# Esquema2.net
KiCad netlist of a schematic drawn in EAGLE
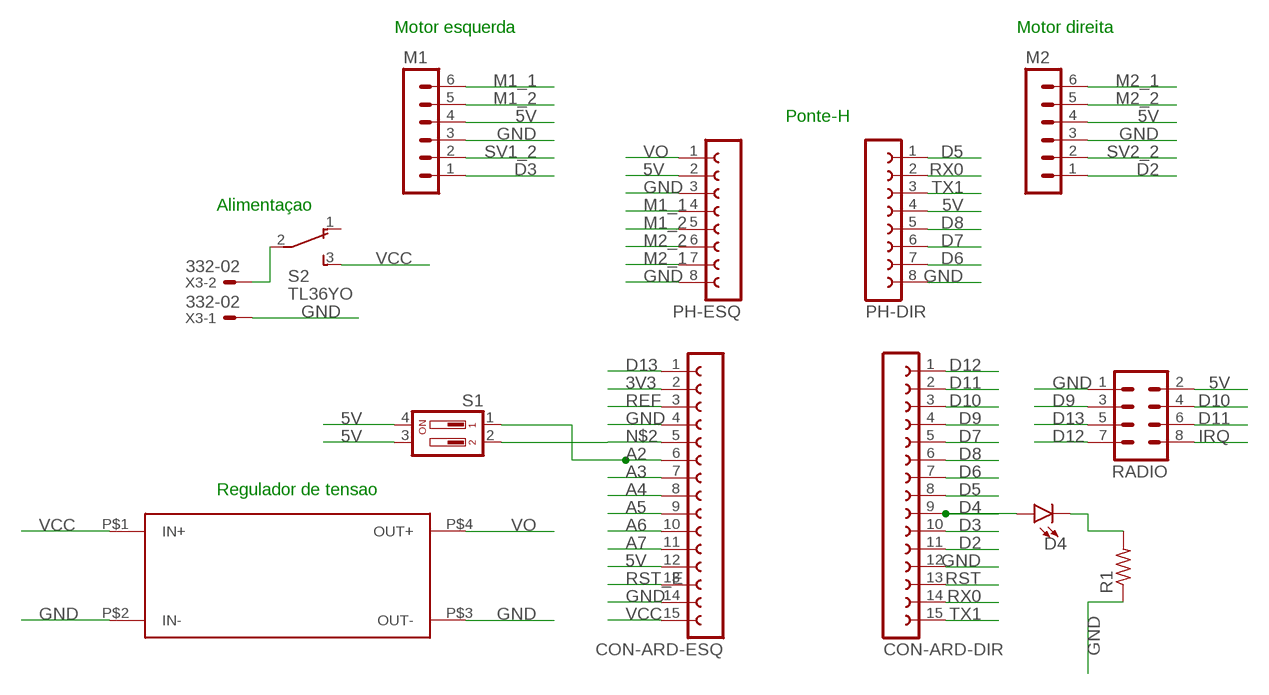
[diagram p0: schematic, sheet 1]

(export (version "E")
  (design (tool "Eeschema 10.0.6"))
  (components
    (comp (ref "CON-ARD-DIR")
      (value "FE15-1")
      (footprint "eagle-import:FE15")
      (libsource (lib "eagle-import") (part "FE15-1"))
    )
    (comp (ref "CON-ARD-ESQ")
      (value "FE15-1")
      (footprint "eagle-import:FE15")
      (fields (field (name "SPICEPREFIX") "X"))
      (libsource (lib "eagle-import") (part "FE15-1"))
    )
    (comp (ref "D4")
      (value "LED-3MM-NO_SILK")
      (footprint "eagle-import:LED_3MM-NS")
      (libsource (lib "eagle-import") (part "LED-3MM-NO_SILK"))
    )
    (comp (ref "M1")
      (value "MA06-1")
      (footprint "eagle-import:MA06-1")
      (libsource (lib "eagle-import") (part "MA06-1"))
    )
    (comp (ref "M2")
      (value "MA06-1")
      (footprint "eagle-import:MA06-1")
      (libsource (lib "eagle-import") (part "MA06-1"))
    )
    (comp (ref "PH-DIR")
      (value "FE08-1")
      (footprint "eagle-import:FE08")
      (libsource (lib "eagle-import") (part "FE08-1"))
    )
    (comp (ref "PH-ESQ")
      (value "FE08-1")
      (footprint "eagle-import:FE08")
      (libsource (lib "eagle-import") (part "FE08-1"))
    )
    (comp (ref "R1")
      (value "R-US_0207/12")
      (footprint "eagle-import:0207_12")
      (libsource (lib "eagle-import") (part "R-US_0207/12"))
    )
    (comp (ref "RADIO")
      (value "MA04-2")
      (footprint "eagle-import:MA04-2")
      (libsource (lib "eagle-import") (part "MA04-2"))
    )
    (comp (ref "S1")
      (value "DA02")
      (footprint "eagle-import:DA-02")
      (libsource (lib "eagle-import") (part "DA02"))
    )
    (comp (ref "S2")
      (value "TL36YO")
      (footprint "eagle-import:TL3XYO")
      (libsource (lib "eagle-import") (part "TL36YO"))
    )
    (comp (ref "U$1")
      (value "REGULADOR")
      (footprint "eagle-import:REGULADOR-FP")
      (libsource (lib "eagle-import") (part "REGULADOR"))
    )
    (comp (ref "X3")
      (value "332-02")
      (footprint "eagle-import:332-02")
      (libsource (lib "eagle-import") (part "332-02"))
    )
  )
  (nets
    (net (code "1") (name "/3V3") (class "Default")
      (node (ref "CON-ARD-ESQ") (pin "2") (pinfunction "2_2") (pintype "passive"))
    )
    (net (code "2") (name "/5V") (class "Default")
      (node (ref "CON-ARD-ESQ") (pin "12") (pinfunction "12_12") (pintype "passive"))
      (node (ref "M1") (pin "4") (pinfunction "4_4") (pintype "passive"))
      (node (ref "M2") (pin "4") (pinfunction "4_4") (pintype "passive"))
      (node (ref "PH-DIR") (pin "4") (pinfunction "4_4") (pintype "passive"))
      (node (ref "PH-ESQ") (pin "2") (pinfunction "2_2") (pintype "passive"))
      (node (ref "RADIO") (pin "2") (pinfunction "2_2") (pintype "passive"))
      (node (ref "S1") (pin "3") (pinfunction "3_3") (pintype "passive"))
      (node (ref "S1") (pin "4") (pinfunction "4_4") (pintype "passive"))
    )
    (net (code "3") (name "/A2") (class "Default")
      (node (ref "CON-ARD-ESQ") (pin "6") (pinfunction "6_6") (pintype "passive"))
      (node (ref "S1") (pin "1") (pinfunction "1_1") (pintype "passive"))
    )
    (net (code "4") (name "/A3") (class "Default")
      (node (ref "CON-ARD-ESQ") (pin "7") (pinfunction "7_7") (pintype "passive"))
    )
    (net (code "5") (name "/A4") (class "Default")
      (node (ref "CON-ARD-ESQ") (pin "8") (pinfunction "8_8") (pintype "passive"))
    )
    (net (code "6") (name "/A5") (class "Default")
      (node (ref "CON-ARD-ESQ") (pin "9") (pinfunction "9_9") (pintype "passive"))
    )
    (net (code "7") (name "/A6") (class "Default")
      (node (ref "CON-ARD-ESQ") (pin "10") (pinfunction "10_10") (pintype "passive"))
    )
    (net (code "8") (name "/A7") (class "Default")
      (node (ref "CON-ARD-ESQ") (pin "11") (pinfunction "11_11") (pintype "passive"))
    )
    (net (code "9") (name "/D2") (class "Default")
      (node (ref "CON-ARD-DIR") (pin "11") (pinfunction "11_11") (pintype "passive"))
      (node (ref "M2") (pin "1") (pinfunction "1_1") (pintype "passive"))
    )
    (net (code "10") (name "/D3") (class "Default")
      (node (ref "CON-ARD-DIR") (pin "10") (pinfunction "10_10") (pintype "passive"))
      (node (ref "M1") (pin "1") (pinfunction "1_1") (pintype "passive"))
    )
    (net (code "11") (name "/D4") (class "Default")
      (node (ref "CON-ARD-DIR") (pin "9") (pinfunction "9_9") (pintype "passive"))
      (node (ref "D4") (pin "A") (pinfunction "A_A") (pintype "passive"))
    )
    (net (code "12") (name "/D5") (class "Default")
      (node (ref "CON-ARD-DIR") (pin "8") (pinfunction "8_8") (pintype "passive"))
      (node (ref "PH-DIR") (pin "1") (pinfunction "1_1") (pintype "passive"))
    )
    (net (code "13") (name "/D6") (class "Default")
      (node (ref "CON-ARD-DIR") (pin "7") (pinfunction "7_7") (pintype "passive"))
      (node (ref "PH-DIR") (pin "7") (pinfunction "7_7") (pintype "passive"))
    )
    (net (code "14") (name "/D7") (class "Default")
      (node (ref "CON-ARD-DIR") (pin "5") (pinfunction "5_5") (pintype "passive"))
      (node (ref "PH-DIR") (pin "6") (pinfunction "6_6") (pintype "passive"))
    )
    (net (code "15") (name "/D8") (class "Default")
      (node (ref "CON-ARD-DIR") (pin "6") (pinfunction "6_6") (pintype "passive"))
      (node (ref "PH-DIR") (pin "5") (pinfunction "5_5") (pintype "passive"))
    )
    (net (code "16") (name "/D9") (class "Default")
      (node (ref "CON-ARD-DIR") (pin "4") (pinfunction "4_4") (pintype "passive"))
      (node (ref "RADIO") (pin "3") (pinfunction "3_3") (pintype "passive"))
    )
    (net (code "17") (name "/D10") (class "Default")
      (node (ref "CON-ARD-DIR") (pin "3") (pinfunction "3_3") (pintype "passive"))
      (node (ref "RADIO") (pin "4") (pinfunction "4_4") (pintype "passive"))
    )
    (net (code "18") (name "/D11") (class "Default")
      (node (ref "CON-ARD-DIR") (pin "2") (pinfunction "2_2") (pintype "passive"))
      (node (ref "RADIO") (pin "6") (pinfunction "6_6") (pintype "passive"))
    )
    (net (code "19") (name "/D12") (class "Default")
      (node (ref "CON-ARD-DIR") (pin "1") (pinfunction "1_1") (pintype "passive"))
      (node (ref "RADIO") (pin "7") (pinfunction "7_7") (pintype "passive"))
    )
    (net (code "20") (name "/D13") (class "Default")
      (node (ref "CON-ARD-ESQ") (pin "1") (pinfunction "1_1") (pintype "passive"))
      (node (ref "RADIO") (pin "5") (pinfunction "5_5") (pintype "passive"))
    )
    (net (code "21") (name "/GND") (class "Default")
      (node (ref "CON-ARD-DIR") (pin "12") (pinfunction "12_12") (pintype "passive"))
      (node (ref "CON-ARD-ESQ") (pin "14") (pinfunction "14_14") (pintype "passive"))
      (node (ref "CON-ARD-ESQ") (pin "4") (pinfunction "4_4") (pintype "passive"))
      (node (ref "M1") (pin "3") (pinfunction "3_3") (pintype "passive"))
      (node (ref "M2") (pin "3") (pinfunction "3_3") (pintype "passive"))
      (node (ref "PH-DIR") (pin "8") (pinfunction "8_8") (pintype "passive"))
      (node (ref "PH-ESQ") (pin "3") (pinfunction "3_3") (pintype "passive"))
      (node (ref "PH-ESQ") (pin "8") (pinfunction "8_8") (pintype "passive"))
      (node (ref "R1") (pin "1") (pinfunction "1_1") (pintype "passive"))
      (node (ref "RADIO") (pin "1") (pinfunction "1_1") (pintype "passive"))
      (node (ref "U$1") (pin "P$2") (pinfunction "IN-_P$2") (pintype "bidirectional"))
      (node (ref "U$1") (pin "P$3") (pinfunction "OUT-_P$3") (pintype "bidirectional"))
      (node (ref "X3") (pin "1") (pinfunction "S_1") (pintype "passive"))
    )
    (net (code "22") (name "/IRQ") (class "Default")
      (node (ref "RADIO") (pin "8") (pinfunction "8_8") (pintype "passive"))
    )
    (net (code "23") (name "/M1_1") (class "Default")
      (node (ref "M1") (pin "6") (pinfunction "6_6") (pintype "passive"))
      (node (ref "PH-ESQ") (pin "4") (pinfunction "4_4") (pintype "passive"))
    )
    (net (code "24") (name "/M1_2") (class "Default")
      (node (ref "M1") (pin "5") (pinfunction "5_5") (pintype "passive"))
      (node (ref "PH-ESQ") (pin "5") (pinfunction "5_5") (pintype "passive"))
    )
    (net (code "25") (name "/M2_1") (class "Default")
      (node (ref "M2") (pin "6") (pinfunction "6_6") (pintype "passive"))
      (node (ref "PH-ESQ") (pin "7") (pinfunction "7_7") (pintype "passive"))
    )
    (net (code "26") (name "/M2_2") (class "Default")
      (node (ref "M2") (pin "5") (pinfunction "5_5") (pintype "passive"))
      (node (ref "PH-ESQ") (pin "6") (pinfunction "6_6") (pintype "passive"))
    )
    (net (code "27") (name "/N$2") (class "Default")
      (node (ref "CON-ARD-ESQ") (pin "5") (pinfunction "5_5") (pintype "passive"))
      (node (ref "S1") (pin "2") (pinfunction "2_2") (pintype "passive"))
    )
    (net (code "28") (name "/REF") (class "Default")
      (node (ref "CON-ARD-ESQ") (pin "3") (pinfunction "3_3") (pintype "passive"))
    )
    (net (code "29") (name "/RST") (class "Default")
      (node (ref "CON-ARD-DIR") (pin "13") (pinfunction "13_13") (pintype "passive"))
    )
    (net (code "30") (name "/RST_E") (class "Default")
      (node (ref "CON-ARD-ESQ") (pin "13") (pinfunction "13_13") (pintype "passive"))
    )
    (net (code "31") (name "/RX0") (class "Default")
      (node (ref "CON-ARD-DIR") (pin "14") (pinfunction "14_14") (pintype "passive"))
      (node (ref "PH-DIR") (pin "2") (pinfunction "2_2") (pintype "passive"))
    )
    (net (code "32") (name "/SV1_2") (class "Default")
      (node (ref "M1") (pin "2") (pinfunction "2_2") (pintype "passive"))
    )
    (net (code "33") (name "/SV2_2") (class "Default")
      (node (ref "M2") (pin "2") (pinfunction "2_2") (pintype "passive"))
    )
    (net (code "34") (name "/TX1") (class "Default")
      (node (ref "CON-ARD-DIR") (pin "15") (pinfunction "15_15") (pintype "passive"))
      (node (ref "PH-DIR") (pin "3") (pinfunction "3_3") (pintype "passive"))
    )
    (net (code "35") (name "/VCC") (class "Default")
      (node (ref "CON-ARD-ESQ") (pin "15") (pinfunction "15_15") (pintype "passive"))
      (node (ref "S2") (pin "3") (pinfunction "S_3") (pintype "passive"))
      (node (ref "U$1") (pin "P$1") (pinfunction "IN+_P$1") (pintype "bidirectional"))
    )
    (net (code "36") (name "/VO") (class "Default")
      (node (ref "PH-ESQ") (pin "1") (pinfunction "1_1") (pintype "passive"))
      (node (ref "U$1") (pin "P$4") (pinfunction "OUT+_P$4") (pintype "bidirectional"))
    )
    (net (code "37") (name "Net-(D4-C)") (class "Default")
      (node (ref "D4") (pin "K") (pinfunction "C_K") (pintype "passive"))
      (node (ref "R1") (pin "2") (pinfunction "2_2") (pintype "passive"))
    )
    (net (code "38") (name "Net-(S2-P)") (class "Default")
      (node (ref "S2") (pin "2") (pinfunction "P_2") (pintype "passive"))
      (node (ref "X3") (pin "2") (pinfunction "S_2") (pintype "passive"))
    )
    (net (code "39") (name "unconnected-(S2-O-Pad1)") (class "Default")
      (node (ref "S2") (pin "1") (pinfunction "O_1") (pintype "passive"))
    )
  )
)
